# Copy_of_ultrasonic_tank_monitor_battery_.net
KiCad netlist of a schematic drawn in Altium Designer
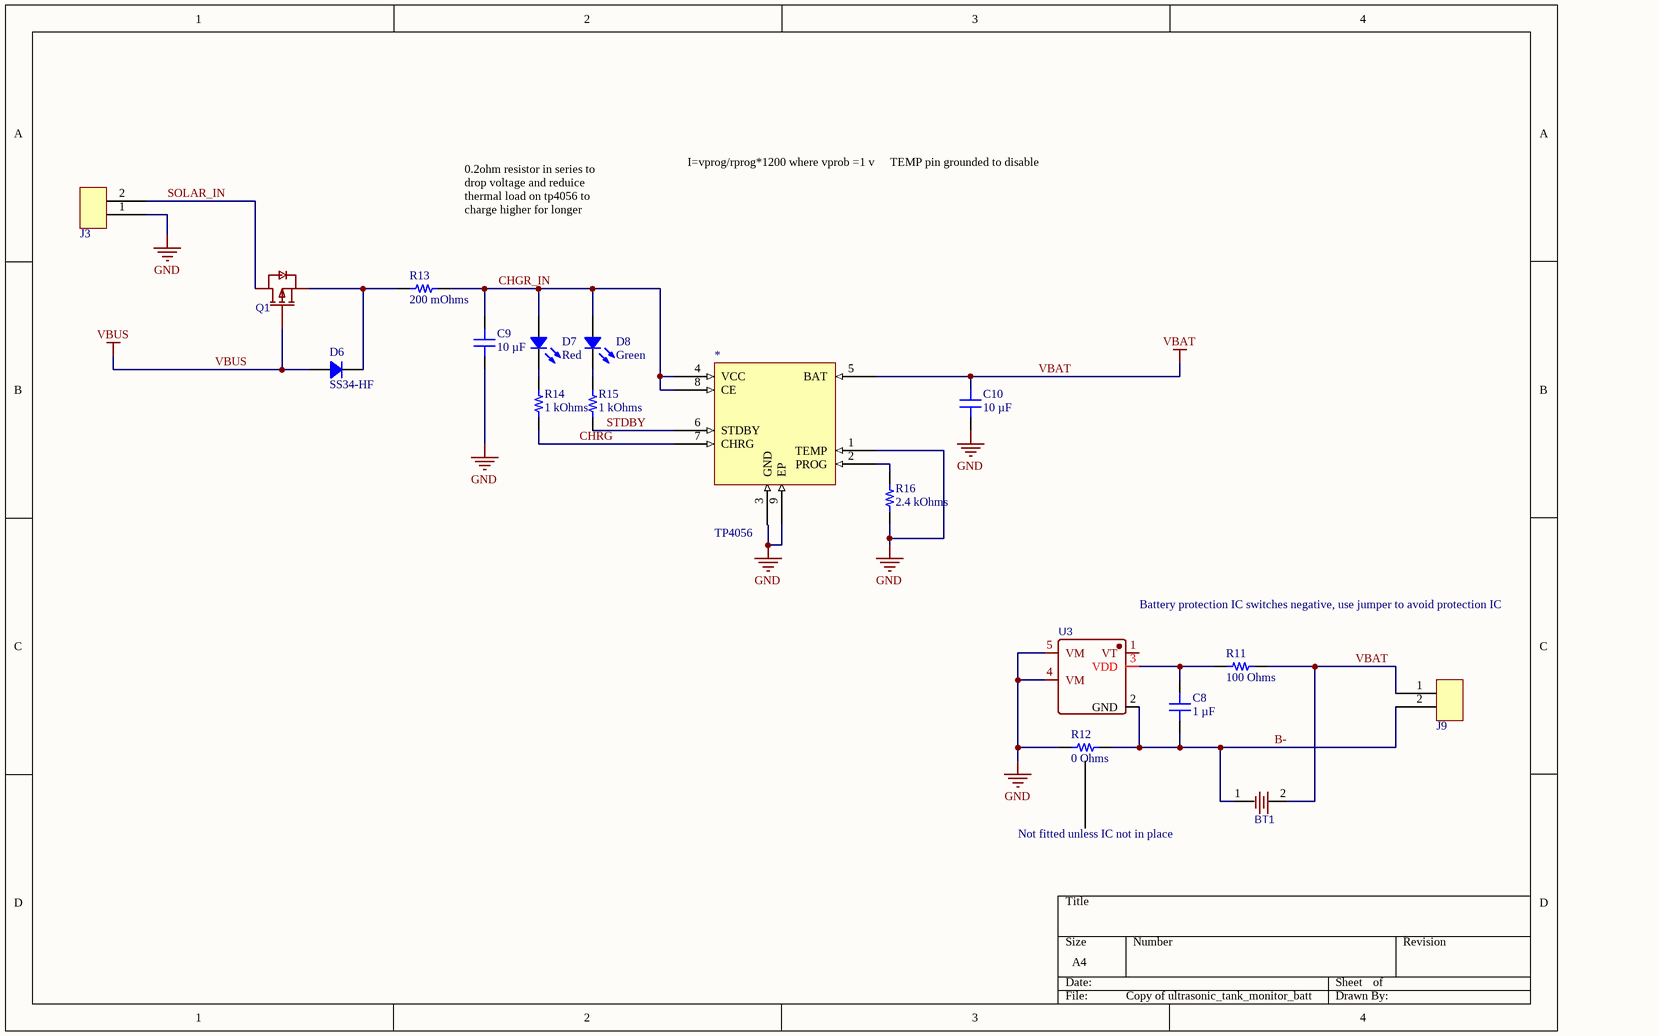
[diagram p0: Copy of ultrasonic_tank_monitor_battery_TP4056.SchDoc]

(export (version "E")
  (design (tool "Eeschema 10.0.6"))
  (components
    (comp (ref "*")
      (value "TP4056")
      (footprint "SOP-8_L4.9-W3.9-P1.27-LS6.0-TL-EP")
      (libsource (lib "Pidgeon_SCH") (part "TP4056"))
    )
    (comp (ref "BT1")
      (value "BH-18650-B1BA002")
      (footprint "BATTERY-SMD_18650-1S-L77.1-W20.7-1")
      (description "18650 SMD battery holder")
      (fields (field (name "MANUFACTURER") "MYOUNG(美阳)") (field (name "CONTRIBUTOR") "lcsc"))
      (libsource (lib "Pidgeon_SCH") (part "18650 SMD battery holder"))
    )
    (comp (ref "C8")
      (value "1 µF")
      (footprint "CAP 0603_1608")
      (description "CAP CER 1UF 10V X7R 0603")
      (fields (field (name "PART NUMBER") "LMK107B7105KAHT") (field (name "MANUFACTURER") "Taiyo Yuden"))
      (libsource (lib "Celestial Altium Library - altium_library") (part "Capacitor"))
    )
    (comp (ref "C9")
      (value "10 µF")
      (footprint "CAP 0603_1608")
      (description "CAP CER 10UF 10V X5R 0603")
      (fields
        (field (name "PART NUMBER") "GRM188R61A106ME69D")
        (field (name "MANUFACTURER") "Murata Electronics")
      )
      (libsource (lib "Celestial Altium Library - altium_library") (part "Capacitor"))
    )
    (comp (ref "C10")
      (value "10 µF")
      (footprint "CAP 0603_1608")
      (description "CAP CER 10UF 10V X5R 0603")
      (fields
        (field (name "PART NUMBER") "GRM188R61A106ME69D")
        (field (name "MANUFACTURER") "Murata Electronics")
      )
      (libsource (lib "Celestial Altium Library - altium_library") (part "Capacitor"))
    )
    (comp (ref "D6")
      (value "SS34-HF")
      (footprint "DO214AC SMA")
      (description "DIODE SCHOTTKY 40V 3A DO214AC")
      (fields (field (name "MANUFACTURER") "Comchip Technology"))
      (libsource (lib "Celestial Altium Library - altium_library") (part "Diode"))
    )
    (comp (ref "D7")
      (value "Red")
      (footprint "LED 0805_2012 RED")
      (description "LED RED 0805 SMD")
      (fields (field (name "PART NUMBER") "5990110007F") (field (name "MANUFACTURER") "Dialight"))
      (libsource (lib "Celestial Altium Library - altium_library") (part "LED"))
    )
    (comp (ref "D8")
      (value "Green")
      (footprint "LED 0805_2012 GREEN")
      (description "LED GREEN 0805 SMD")
      (fields (field (name "PART NUMBER") "5990181007F") (field (name "MANUFACTURER") "Dialight"))
      (libsource (lib "Celestial Altium Library - altium_library") (part "LED"))
    )
    (comp (ref "J3")
      (value "B2B-PH-K-S")
      (footprint "CONN-TH_B2B-PH-K-S")
      (description "2 Pin JST PH 2.0 Connector Straight")
      (libsource (lib "Pidgeon_SCH") (part "B2B-PH-K-S"))
    )
    (comp (ref "J9")
      (value "S2B-PH-K-S")
      (footprint "CONN-TH_S2B-PH-K-S-LF-SN")
      (description "2 Pin JST PH 2.0 Connector RA")
      (libsource (lib "Pidgeon_SCH") (part "S2B-PH-K-S"))
    )
    (comp (ref "Q1")
      (value "SI2301-ZE")
      (footprint "SOT-23-3_L2.9-W1.3-P1.90-LS2.4-BR")
      (description "P-CHAN Mosfet SI2301")
      (fields (field (name "MANUFACTURER") "HXY MOSFET(华轩阳电子)") (field (name "CONTRIBUTOR") "lcsc"))
      (libsource (lib "Pidgeon_SCH") (part "SI2301-ZE"))
    )
    (comp (ref "R11")
      (value "100 Ohms")
      (footprint "RES 0603_1608")
      (description "RES 100 OHM 5% 1/10W 0603")
      (fields
        (field (name "PART NUMBER") "WR06X101 JTL")
        (field (name "MANUFACTURER") "Walsin Technology Corporation")
      )
      (libsource (lib "Celestial Altium Library - altium_library") (part "Resistor"))
    )
    (comp (ref "R12")
      (value "0 Ohms")
      (footprint "RES 1206_3216")
      (description "RES SMD 0 OHM 3/4W 1206 WIDE")
      (fields (field (name "PART NUMBER") "RCL06120000Z0EA") (field (name "MANUFACTURER") "Vishay Dale"))
      (libsource (lib "Celestial Altium Library - altium_library") (part "Resistor"))
    )
    (comp (ref "R13")
      (value "200 mOhms")
      (footprint "RES 1206_3216")
      (description "RES 0.2 OHM 1% 1/2W 1206")
      (fields (field (name "PART NUMBER") "PT1206FR-7W0R2L") (field (name "MANUFACTURER") "Yageo"))
      (libsource (lib "Celestial Altium Library - altium_library") (part "Resistor"))
    )
    (comp (ref "R14")
      (value "1 kOhms")
      (footprint "RES 0603_1608")
      (description "RES 1K OHM 5% 1/4W 0603")
      (fields (field (name "PART NUMBER") "SR0603JR-7T1KL") (field (name "MANUFACTURER") "Yageo"))
      (libsource (lib "Celestial Altium Library - altium_library") (part "Resistor"))
    )
    (comp (ref "R15")
      (value "1 kOhms")
      (footprint "RES 0603_1608")
      (description "RES 1K OHM 5% 1/4W 0603")
      (fields (field (name "PART NUMBER") "SR0603JR-7T1KL") (field (name "MANUFACTURER") "Yageo"))
      (libsource (lib "Celestial Altium Library - altium_library") (part "Resistor"))
    )
    (comp (ref "R16")
      (value "2.4 kOhms")
      (footprint "RES 0603_1608")
      (description "RES 2.4K OHM 5% 0.3W 0603")
      (fields (field (name "PART NUMBER") "SDR03EZPJ242") (field (name "MANUFACTURER") "Rohm Semiconductor"))
      (libsource (lib "Celestial Altium Library - altium_library") (part "Resistor"))
    )
    (comp (ref "U3")
      (value "SKCL3130ME")
      (footprint "SOT-23-5_L2.9-W1.6-P0.95-LS2.8-BR")
      (description "1 cell battery protection IC Li-ion OC OV UV SOT 23-5")
      (fields (field (name "MANUFACTURER") "SHIKUES(时科)") (field (name "CONTRIBUTOR") "LCSC"))
      (libsource (lib "Pidgeon_SCH") (part "SKCL3130ME"))
    )
  )
  (nets
    (net (code "1") (name "/B-") (class "Default")
      (node (ref "BT1") (pin "1") (pinfunction "1_1") (pintype "passive"))
      (node (ref "C8") (pin "2") (pinfunction "2_2") (pintype "passive"))
      (node (ref "J9") (pin "2") (pintype "power_in"))
      (node (ref "R12") (pin "2") (pinfunction "2_2") (pintype "passive"))
      (node (ref "U3") (pin "2") (pinfunction "GND_2") (pintype "passive"))
    )
    (net (code "2") (name "/CHGR_IN") (class "Default")
      (node (ref "*") (pin "4") (pinfunction "VCC_4") (pintype "input"))
      (node (ref "*") (pin "8") (pinfunction "CE_8") (pintype "input"))
      (node (ref "C9") (pin "2") (pinfunction "2_2") (pintype "passive"))
      (node (ref "D7") (pin "1") (pinfunction "1_1") (pintype "passive"))
      (node (ref "D8") (pin "1") (pinfunction "1_1") (pintype "passive"))
      (node (ref "R13") (pin "2") (pinfunction "2_2") (pintype "passive"))
    )
    (net (code "3") (name "/CHRG") (class "Default")
      (node (ref "*") (pin "7") (pinfunction "CHRG_7") (pintype "input"))
      (node (ref "R14") (pin "2") (pinfunction "2_2") (pintype "passive"))
    )
    (net (code "4") (name "/SOLAR_IN") (class "Default")
      (node (ref "J3") (pin "2") (pintype "power_in"))
      (node (ref "Q1") (pin "3") (pinfunction "D_3") (pintype "passive"))
    )
    (net (code "5") (name "/STDBY") (class "Default")
      (node (ref "*") (pin "6") (pinfunction "STDBY_6") (pintype "input"))
      (node (ref "R15") (pin "2") (pinfunction "2_2") (pintype "passive"))
    )
    (net (code "6") (name "GND") (class "Default")
      (node (ref "*") (pin "1") (pinfunction "TEMP_1") (pintype "input"))
      (node (ref "*") (pin "9") (pinfunction "EP_9") (pintype "input"))
      (node (ref "C10") (pin "1") (pinfunction "1_1") (pintype "passive"))
      (node (ref "C9") (pin "1") (pinfunction "1_1") (pintype "passive"))
      (node (ref "J3") (pin "1") (pintype "power_in"))
      (node (ref "R12") (pin "1") (pinfunction "1_1") (pintype "passive"))
      (node (ref "R16") (pin "1") (pinfunction "1_1") (pintype "passive"))
      (node (ref "U3") (pin "4") (pinfunction "VM_4") (pintype "passive"))
      (node (ref "U3") (pin "5") (pinfunction "VM_5") (pintype "passive"))
    )
    (net (code "7") (name "Net-(*-PROG)") (class "Default")
      (node (ref "*") (pin "2") (pinfunction "PROG_2") (pintype "input"))
      (node (ref "R16") (pin "2") (pinfunction "2_2") (pintype "passive"))
    )
    (net (code "8") (name "Net-(D7-Pad2)") (class "Default")
      (node (ref "D7") (pin "2") (pinfunction "2_2") (pintype "passive"))
      (node (ref "R14") (pin "1") (pinfunction "1_1") (pintype "passive"))
    )
    (net (code "9") (name "Net-(D8-Pad2)") (class "Default")
      (node (ref "D8") (pin "2") (pinfunction "2_2") (pintype "passive"))
      (node (ref "R15") (pin "1") (pinfunction "1_1") (pintype "passive"))
    )
    (net (code "10") (name "Net-(Q1-S)") (class "Default")
      (node (ref "D6") (pin "2") (pinfunction "2_2") (pintype "passive"))
      (node (ref "Q1") (pin "2") (pinfunction "S_2") (pintype "passive"))
      (node (ref "R13") (pin "1") (pinfunction "1_1") (pintype "passive"))
    )
    (net (code "11") (name "Net-(U3-VDD)") (class "Default")
      (node (ref "C8") (pin "1") (pinfunction "1_1") (pintype "passive"))
      (node (ref "R11") (pin "1") (pinfunction "1_1") (pintype "passive"))
      (node (ref "U3") (pin "3") (pinfunction "VDD_3") (pintype "passive"))
    )
    (net (code "12") (name "VBAT") (class "Default")
      (node (ref "*") (pin "5") (pinfunction "BAT_5") (pintype "input"))
      (node (ref "BT1") (pin "2") (pinfunction "2_2") (pintype "passive"))
      (node (ref "C10") (pin "2") (pinfunction "2_2") (pintype "passive"))
      (node (ref "J9") (pin "1") (pintype "power_in"))
      (node (ref "R11") (pin "2") (pinfunction "2_2") (pintype "passive"))
    )
    (net (code "13") (name "VBUS") (class "Default")
      (node (ref "D6") (pin "1") (pinfunction "1_1") (pintype "passive"))
      (node (ref "Q1") (pin "1") (pinfunction "G_1") (pintype "passive"))
    )
    (net (code "14") (name "unconnected-(*-GND-Pad3)") (class "Default")
      (node (ref "*") (pin "3") (pinfunction "GND_3") (pintype "input"))
    )
    (net (code "15") (name "unconnected-(U3-VT-Pad1)") (class "Default")
      (node (ref "U3") (pin "1") (pinfunction "VT_1") (pintype "passive"))
    )
  )
)
